# working.net
KiCad netlist of a schematic drawn in EAGLE
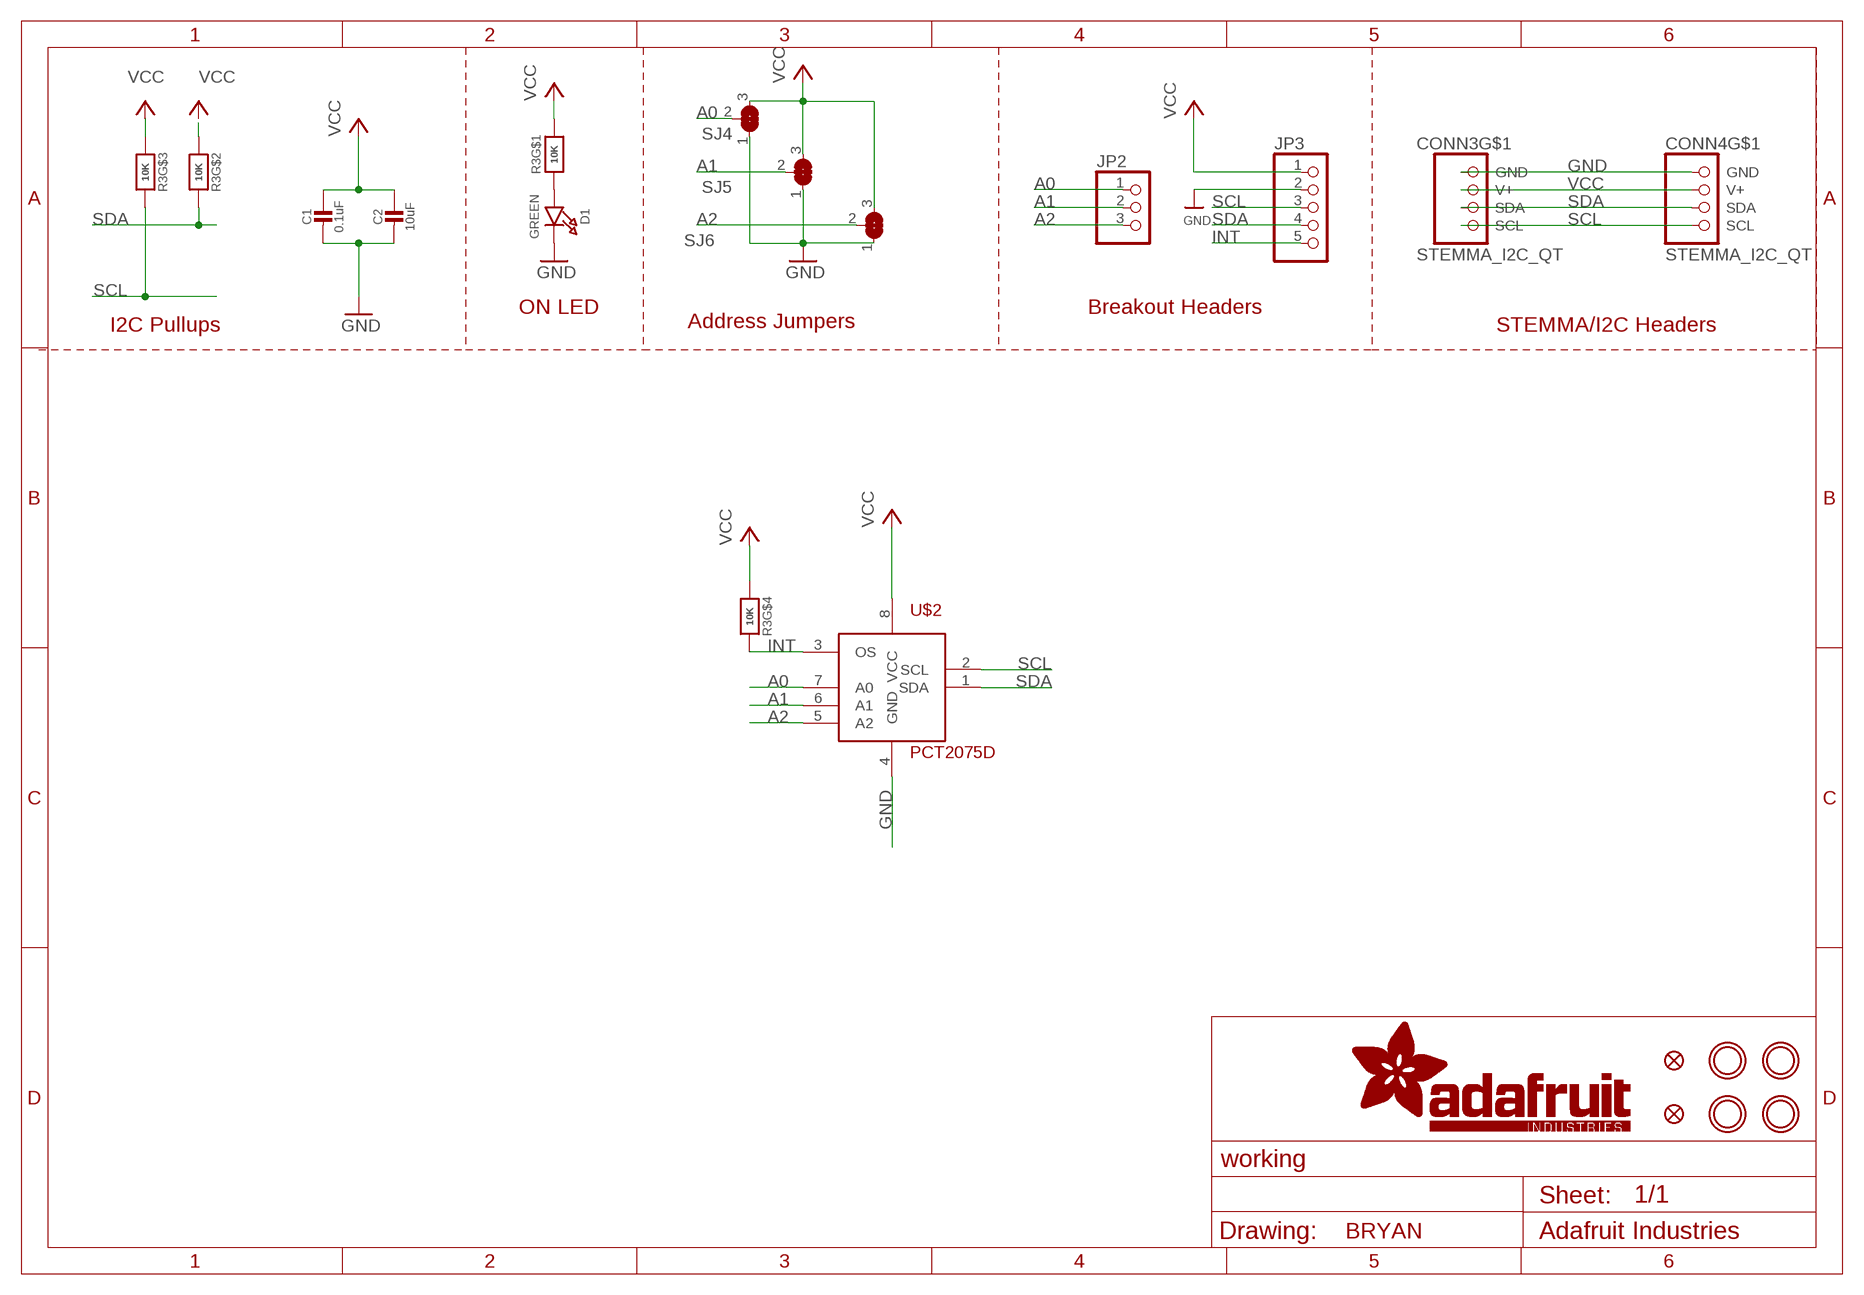
[diagram p0: schematic, sheet 1]

(export (version "E")
  (design (tool "Eeschema 10.0.6"))
  (components
    (comp (ref "C1")
      (value "0.1uF")
      (footprint "eagle-import:0603-NO")
      (libsource (lib "eagle-import") (part "CAP_CERAMIC0603_NO"))
    )
    (comp (ref "C2")
      (value "10uF")
      (footprint "eagle-import:0805-NO")
      (libsource (lib "eagle-import") (part "CAP_CERAMIC0805-NOOUTLINE"))
    )
    (comp (ref "CONN3")
      (value "STEMMA_I2C_QT")
      (footprint "eagle-import:JST_SH4")
      (libsource (lib "eagle-import") (part "STEMMA_I2C_QT"))
    )
    (comp (ref "CONN4")
      (value "STEMMA_I2C_QT")
      (footprint "eagle-import:JST_SH4")
      (libsource (lib "eagle-import") (part "STEMMA_I2C_QT"))
    )
    (comp (ref "D1")
      (value "GREEN")
      (footprint "eagle-import:CHIPLED_0603_NOOUTLINE")
      (libsource (lib "eagle-import") (part "LED0603_NOOUTLINE"))
    )
    (comp (ref "FID3")
      (value "FIDUCIAL_1MM")
      (footprint "eagle-import:FIDUCIAL_1MM")
      (libsource (lib "eagle-import") (part "FIDUCIAL_1MM"))
    )
    (comp (ref "FID4")
      (value "FIDUCIAL_1MM")
      (footprint "eagle-import:FIDUCIAL_1MM")
      (libsource (lib "eagle-import") (part "FIDUCIAL_1MM"))
    )
    (comp (ref "JP2")
      (value "HEADER-1X3ROUND")
      (footprint "eagle-import:1X03_ROUND")
      (libsource (lib "eagle-import") (part "HEADER-1X3ROUND"))
    )
    (comp (ref "JP3")
      (value "HEADER-1X5ROUND")
      (footprint "eagle-import:1X05_ROUND")
      (libsource (lib "eagle-import") (part "HEADER-1X5ROUND"))
    )
    (comp (ref "R3")
      (value "10K")
      (footprint "eagle-import:RESPACK_4X0603")
      (libsource (lib "eagle-import") (part "RESISTOR_4PACK"))
    )
    (comp (ref "SJ4")
      (value "SOLDERJUMPER_2WAY")
      (footprint "eagle-import:SOLDERJUMPER_2WAY_OPEN_NOPASTE")
      (libsource (lib "eagle-import") (part "SOLDERJUMPER_2WAY"))
    )
    (comp (ref "SJ5")
      (value "SOLDERJUMPER_2WAY")
      (footprint "eagle-import:SOLDERJUMPER_2WAY_OPEN_NOPASTE")
      (libsource (lib "eagle-import") (part "SOLDERJUMPER_2WAY"))
    )
    (comp (ref "SJ6")
      (value "SOLDERJUMPER_2WAY")
      (footprint "eagle-import:SOLDERJUMPER_2WAY_OPEN_NOPASTE")
      (libsource (lib "eagle-import") (part "SOLDERJUMPER_2WAY"))
    )
    (comp (ref "U$1")
      (value "MOUNTINGHOLE2.5")
      (footprint "eagle-import:MOUNTINGHOLE_2.5_PLATED")
      (libsource (lib "eagle-import") (part "MOUNTINGHOLE2.5"))
    )
    (comp (ref "U$2")
      (value "PCT2075D")
      (footprint "eagle-import:SOIC8_150MIL")
      (libsource (lib "eagle-import") (part "PCT2075D"))
    )
    (comp (ref "U$17")
      (value "MOUNTINGHOLE2.5")
      (footprint "eagle-import:MOUNTINGHOLE_2.5_PLATED")
      (libsource (lib "eagle-import") (part "MOUNTINGHOLE2.5"))
    )
    (comp (ref "U$19")
      (value "MOUNTINGHOLE2.5")
      (footprint "eagle-import:MOUNTINGHOLE_2.5_PLATED")
      (libsource (lib "eagle-import") (part "MOUNTINGHOLE2.5"))
    )
    (comp (ref "U$21")
      (value "MOUNTINGHOLE2.5")
      (footprint "eagle-import:MOUNTINGHOLE_2.5_PLATED")
      (libsource (lib "eagle-import") (part "MOUNTINGHOLE2.5"))
    )
  )
  (nets
    (net (code "1") (name "/A0") (class "Default")
      (node (ref "JP2") (pin "1") (pinfunction "1_1") (pintype "passive"))
      (node (ref "SJ4") (pin "2") (pinfunction "2_2") (pintype "passive"))
      (node (ref "U$2") (pin "7") (pinfunction "A0_7") (pintype "input"))
    )
    (net (code "2") (name "/A1") (class "Default")
      (node (ref "JP2") (pin "2") (pinfunction "2_2") (pintype "passive"))
      (node (ref "SJ5") (pin "2") (pinfunction "2_2") (pintype "passive"))
      (node (ref "U$2") (pin "6") (pinfunction "A1_6") (pintype "input"))
    )
    (net (code "3") (name "/A2") (class "Default")
      (node (ref "JP2") (pin "3") (pinfunction "3_3") (pintype "passive"))
      (node (ref "SJ6") (pin "2") (pinfunction "2_2") (pintype "passive"))
      (node (ref "U$2") (pin "5") (pinfunction "A2_5") (pintype "input"))
    )
    (net (code "4") (name "/INT") (class "Default")
      (node (ref "JP3") (pin "5") (pinfunction "5_5") (pintype "passive"))
      (node (ref "R3") (pin "5") (pinfunction "2_5") (pintype "passive"))
      (node (ref "U$2") (pin "3") (pinfunction "OS_3") (pintype "output"))
    )
    (net (code "5") (name "/SCL") (class "Default")
      (node (ref "CONN3") (pin "4") (pinfunction "SCL_4") (pintype "passive"))
      (node (ref "CONN4") (pin "4") (pinfunction "SCL_4") (pintype "passive"))
      (node (ref "JP3") (pin "3") (pinfunction "3_3") (pintype "passive"))
      (node (ref "R3") (pin "6") (pinfunction "2_6") (pintype "passive"))
      (node (ref "U$2") (pin "2") (pinfunction "SCL_2") (pintype "bidirectional"))
    )
    (net (code "6") (name "/SDA") (class "Default")
      (node (ref "CONN3") (pin "3") (pinfunction "SDA_3") (pintype "passive"))
      (node (ref "CONN4") (pin "3") (pinfunction "SDA_3") (pintype "passive"))
      (node (ref "JP3") (pin "4") (pinfunction "4_4") (pintype "passive"))
      (node (ref "R3") (pin "7") (pinfunction "2_7") (pintype "passive"))
      (node (ref "U$2") (pin "1") (pinfunction "SDA_1") (pintype "bidirectional"))
    )
    (net (code "7") (name "GND") (class "Default")
      (node (ref "C1") (pin "2") (pinfunction "2_2") (pintype "passive"))
      (node (ref "C2") (pin "2") (pinfunction "2_2") (pintype "passive"))
      (node (ref "CONN3") (pin "1") (pinfunction "GND_1") (pintype "passive"))
      (node (ref "CONN4") (pin "1") (pinfunction "GND_1") (pintype "passive"))
      (node (ref "D1") (pin "C") (pinfunction "C_C") (pintype "passive"))
      (node (ref "JP3") (pin "2") (pinfunction "2_2") (pintype "passive"))
      (node (ref "SJ4") (pin "1") (pinfunction "1_1") (pintype "passive"))
      (node (ref "SJ5") (pin "1") (pinfunction "1_1") (pintype "passive"))
      (node (ref "SJ6") (pin "1") (pinfunction "1_1") (pintype "passive"))
      (node (ref "U$2") (pin "4") (pinfunction "GND_4") (pintype "power_in"))
    )
    (net (code "8") (name "Net-(D1-PadA)") (class "Default")
      (node (ref "D1") (pin "A") (pinfunction "A_A") (pintype "passive"))
      (node (ref "R3") (pin "1") (pinfunction "1_1") (pintype "passive"))
    )
    (net (code "9") (name "VCC") (class "Default")
      (node (ref "C1") (pin "1") (pinfunction "1_1") (pintype "passive"))
      (node (ref "C2") (pin "1") (pinfunction "1_1") (pintype "passive"))
      (node (ref "CONN3") (pin "2") (pinfunction "V+_2") (pintype "passive"))
      (node (ref "CONN4") (pin "2") (pinfunction "V+_2") (pintype "passive"))
      (node (ref "JP3") (pin "1") (pinfunction "1_1") (pintype "passive"))
      (node (ref "R3") (pin "2") (pinfunction "1_2") (pintype "passive"))
      (node (ref "R3") (pin "3") (pinfunction "1_3") (pintype "passive"))
      (node (ref "R3") (pin "4") (pinfunction "1_4") (pintype "passive"))
      (node (ref "R3") (pin "8") (pinfunction "2_8") (pintype "passive"))
      (node (ref "SJ4") (pin "3") (pinfunction "3_3") (pintype "passive"))
      (node (ref "SJ5") (pin "3") (pinfunction "3_3") (pintype "passive"))
      (node (ref "SJ6") (pin "3") (pinfunction "3_3") (pintype "passive"))
      (node (ref "U$2") (pin "8") (pinfunction "VCC_8") (pintype "power_in"))
    )
  )
)
